# HyperRAM2.net
KiCad netlist of a schematic drawn in Altium Designer
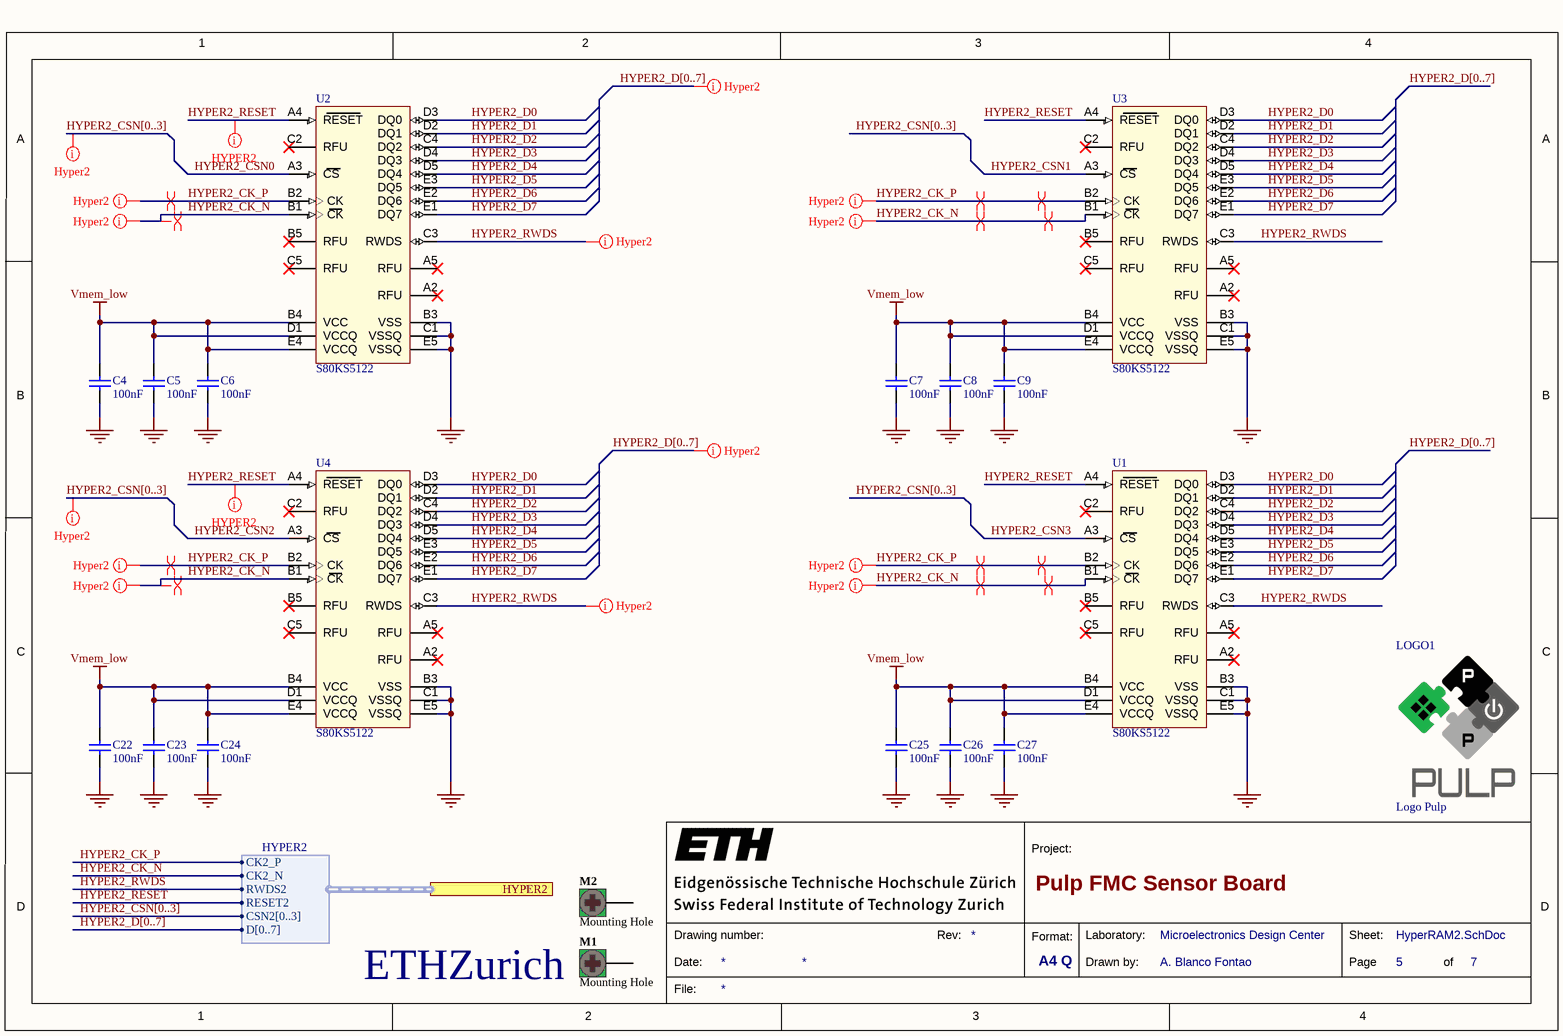
[diagram p0: HyperRAM2.SchDoc]

(export (version "E")
  (design (tool "Eeschema 10.0.6"))
  (components
    (comp (ref "A1")
      (value "Logo ETH Zurich")
      (footprint "eth-zurich_3mm")
      (libsource (lib "ETHZ Vault") (part "CMP-00038-1"))
    )
    (comp (ref "C4")
      (value "100nF")
      (footprint "CAPC0603(1608)100_N")
      (description "CAP 100nF 25V ±10% 0603 (1608 Metric) Thickness 1mm SMD")
      (fields (field (name "TOLERANCE") "Â±10%") (field (name "Comment") "CAP 100nF 25V 0603(1608)"))
      (libsource (lib "Altium Content Vault") (part "CMP-1035-02588-1"))
    )
    (comp (ref "C5")
      (value "100nF")
      (footprint "CAPC0603(1608)100_N")
      (description "CAP 100nF 25V ±10% 0603 (1608 Metric) Thickness 1mm SMD")
      (fields (field (name "TOLERANCE") "Â±10%") (field (name "Comment") "CAP 100nF 25V 0603(1608)"))
      (libsource (lib "Altium Content Vault") (part "CMP-1035-02588-1"))
    )
    (comp (ref "C6")
      (value "100nF")
      (footprint "CAPC0603(1608)100_N")
      (description "CAP 100nF 25V ±10% 0603 (1608 Metric) Thickness 1mm SMD")
      (fields (field (name "TOLERANCE") "Â±10%") (field (name "Comment") "CAP 100nF 25V 0603(1608)"))
      (libsource (lib "Altium Content Vault") (part "CMP-1035-02588-1"))
    )
    (comp (ref "C7")
      (value "100nF")
      (footprint "CAPC0603(1608)100_N")
      (description "CAP 100nF 25V ±10% 0603 (1608 Metric) Thickness 1mm SMD")
      (fields (field (name "TOLERANCE") "Â±10%") (field (name "Comment") "CAP 100nF 25V 0603(1608)"))
      (libsource (lib "Altium Content Vault") (part "CMP-1035-02588-1"))
    )
    (comp (ref "C8")
      (value "100nF")
      (footprint "CAPC0603(1608)100_N")
      (description "CAP 100nF 25V ±10% 0603 (1608 Metric) Thickness 1mm SMD")
      (fields (field (name "TOLERANCE") "Â±10%") (field (name "Comment") "CAP 100nF 25V 0603(1608)"))
      (libsource (lib "Altium Content Vault") (part "CMP-1035-02588-1"))
    )
    (comp (ref "C9")
      (value "100nF")
      (footprint "CAPC0603(1608)100_N")
      (description "CAP 100nF 25V ±10% 0603 (1608 Metric) Thickness 1mm SMD")
      (fields (field (name "TOLERANCE") "Â±10%") (field (name "Comment") "CAP 100nF 25V 0603(1608)"))
      (libsource (lib "Altium Content Vault") (part "CMP-1035-02588-1"))
    )
    (comp (ref "C22")
      (value "100nF")
      (footprint "CAPC0603(1608)100_N")
      (description "CAP 100nF 25V ±10% 0603 (1608 Metric) Thickness 1mm SMD")
      (fields (field (name "TOLERANCE") "Â±10%") (field (name "Comment") "CAP 100nF 25V 0603(1608)"))
      (libsource (lib "Altium Content Vault") (part "CMP-1035-02588-1"))
    )
    (comp (ref "C23")
      (value "100nF")
      (footprint "CAPC0603(1608)100_N")
      (description "CAP 100nF 25V ±10% 0603 (1608 Metric) Thickness 1mm SMD")
      (fields (field (name "TOLERANCE") "Â±10%") (field (name "Comment") "CAP 100nF 25V 0603(1608)"))
      (libsource (lib "Altium Content Vault") (part "CMP-1035-02588-1"))
    )
    (comp (ref "C24")
      (value "100nF")
      (footprint "CAPC0603(1608)100_N")
      (description "CAP 100nF 25V ±10% 0603 (1608 Metric) Thickness 1mm SMD")
      (fields (field (name "TOLERANCE") "Â±10%") (field (name "Comment") "CAP 100nF 25V 0603(1608)"))
      (libsource (lib "Altium Content Vault") (part "CMP-1035-02588-1"))
    )
    (comp (ref "C25")
      (value "100nF")
      (footprint "CAPC0603(1608)100_N")
      (description "CAP 100nF 25V ±10% 0603 (1608 Metric) Thickness 1mm SMD")
      (fields (field (name "TOLERANCE") "Â±10%") (field (name "Comment") "CAP 100nF 25V 0603(1608)"))
      (libsource (lib "Altium Content Vault") (part "CMP-1035-02588-1"))
    )
    (comp (ref "C26")
      (value "100nF")
      (footprint "CAPC0603(1608)100_N")
      (description "CAP 100nF 25V ±10% 0603 (1608 Metric) Thickness 1mm SMD")
      (fields (field (name "TOLERANCE") "Â±10%") (field (name "Comment") "CAP 100nF 25V 0603(1608)"))
      (libsource (lib "Altium Content Vault") (part "CMP-1035-02588-1"))
    )
    (comp (ref "C27")
      (value "100nF")
      (footprint "CAPC0603(1608)100_N")
      (description "CAP 100nF 25V ±10% 0603 (1608 Metric) Thickness 1mm SMD")
      (fields (field (name "TOLERANCE") "Â±10%") (field (name "Comment") "CAP 100nF 25V 0603(1608)"))
      (libsource (lib "Altium Content Vault") (part "CMP-1035-02588-1"))
    )
    (comp (ref "LOGO1")
      (value "Logo Pulp")
      (footprint "Logo Pulp")
      (description "4 Layers: only valid for layer stack as defined for the TestBoards")
      (libsource (lib "ETHZ Vault") (part "CMP-00145-1"))
    )
    (comp (ref "M1")
      (value "Mounting Hole")
      (footprint "Hole M3")
      (description "Mounting Hole, 7.2mm pad, 3.2mm plated hole")
      (libsource (lib "ETHZ Vault") (part "Hole"))
    )
    (comp (ref "M2")
      (value "Mounting Hole")
      (footprint "Hole M3")
      (description "Mounting Hole, 7.2mm pad, 3.2mm plated hole")
      (libsource (lib "ETHZ Vault") (part "Hole"))
    )
    (comp (ref "U1")
      (value "S80KS5122")
      (footprint "FBGA24_A-130")
      (description "512 Mb: HYPERRAM™ self-refresh dynamic\r\nRAM (DRAM) with HYPERBUS™ interface\r\n1.8 V")
      (libsource (lib "hyperRAM") (part "S80KS5122"))
    )
    (comp (ref "U2")
      (value "S80KS5122")
      (footprint "FBGA24_A-130")
      (description "512 Mb: HYPERRAM™ self-refresh dynamic\r\nRAM (DRAM) with HYPERBUS™ interface\r\n1.8 V")
      (libsource (lib "hyperRAM") (part "S80KS5122"))
    )
    (comp (ref "U3")
      (value "S80KS5122")
      (footprint "FBGA24_A-130")
      (description "512 Mb: HYPERRAM™ self-refresh dynamic\r\nRAM (DRAM) with HYPERBUS™ interface\r\n1.8 V")
      (libsource (lib "hyperRAM") (part "S80KS5122"))
    )
    (comp (ref "U4")
      (value "S80KS5122")
      (footprint "FBGA24_A-130")
      (description "512 Mb: HYPERRAM™ self-refresh dynamic\r\nRAM (DRAM) with HYPERBUS™ interface\r\n1.8 V")
      (libsource (lib "hyperRAM") (part "S80KS5122"))
    )
  )
  (nets
    (net (code "2") (name "/HYPER2_CK_N") (class "Default")
      (node (ref "U1") (pin "B1") (pinfunction "CK_B1") (pintype "input"))
      (node (ref "U2") (pin "B1") (pinfunction "CK_B1") (pintype "input"))
      (node (ref "U3") (pin "B1") (pinfunction "CK_B1") (pintype "input"))
      (node (ref "U4") (pin "B1") (pinfunction "CK_B1") (pintype "input"))
    )
    (net (code "3") (name "/HYPER2_CK_P") (class "Default")
      (node (ref "U1") (pin "B2") (pinfunction "CK_B2") (pintype "input"))
      (node (ref "U2") (pin "B2") (pinfunction "CK_B2") (pintype "input"))
      (node (ref "U3") (pin "B2") (pinfunction "CK_B2") (pintype "input"))
      (node (ref "U4") (pin "B2") (pinfunction "CK_B2") (pintype "input"))
    )
    (net (code "4") (name "/HYPER2_CSN0") (class "Default")
      (node (ref "U2") (pin "A3") (pinfunction "CS_A3") (pintype "input"))
    )
    (net (code "5") (name "/HYPER2_CSN1") (class "Default")
      (node (ref "U3") (pin "A3") (pinfunction "CS_A3") (pintype "input"))
    )
    (net (code "6") (name "/HYPER2_CSN2") (class "Default")
      (node (ref "U4") (pin "A3") (pinfunction "CS_A3") (pintype "input"))
    )
    (net (code "7") (name "/HYPER2_CSN3") (class "Default")
      (node (ref "U1") (pin "A3") (pinfunction "CS_A3") (pintype "input"))
    )
    (net (code "9") (name "/HYPER2_D0") (class "Default")
      (node (ref "U1") (pin "D3") (pinfunction "DQ0_D3") (pintype "bidirectional"))
      (node (ref "U2") (pin "D3") (pinfunction "DQ0_D3") (pintype "bidirectional"))
      (node (ref "U3") (pin "D3") (pinfunction "DQ0_D3") (pintype "bidirectional"))
      (node (ref "U4") (pin "D3") (pinfunction "DQ0_D3") (pintype "bidirectional"))
    )
    (net (code "10") (name "/HYPER2_D1") (class "Default")
      (node (ref "U1") (pin "D2") (pinfunction "DQ1_D2") (pintype "bidirectional"))
      (node (ref "U2") (pin "D2") (pinfunction "DQ1_D2") (pintype "bidirectional"))
      (node (ref "U3") (pin "D2") (pinfunction "DQ1_D2") (pintype "bidirectional"))
      (node (ref "U4") (pin "D2") (pinfunction "DQ1_D2") (pintype "bidirectional"))
    )
    (net (code "11") (name "/HYPER2_D2") (class "Default")
      (node (ref "U1") (pin "C4") (pinfunction "DQ2_C4") (pintype "bidirectional"))
      (node (ref "U2") (pin "C4") (pinfunction "DQ2_C4") (pintype "bidirectional"))
      (node (ref "U3") (pin "C4") (pinfunction "DQ2_C4") (pintype "bidirectional"))
      (node (ref "U4") (pin "C4") (pinfunction "DQ2_C4") (pintype "bidirectional"))
    )
    (net (code "12") (name "/HYPER2_D3") (class "Default")
      (node (ref "U1") (pin "D4") (pinfunction "DQ3_D4") (pintype "bidirectional"))
      (node (ref "U2") (pin "D4") (pinfunction "DQ3_D4") (pintype "bidirectional"))
      (node (ref "U3") (pin "D4") (pinfunction "DQ3_D4") (pintype "bidirectional"))
      (node (ref "U4") (pin "D4") (pinfunction "DQ3_D4") (pintype "bidirectional"))
    )
    (net (code "13") (name "/HYPER2_D4") (class "Default")
      (node (ref "U1") (pin "D5") (pinfunction "DQ4_D5") (pintype "bidirectional"))
      (node (ref "U2") (pin "D5") (pinfunction "DQ4_D5") (pintype "bidirectional"))
      (node (ref "U3") (pin "D5") (pinfunction "DQ4_D5") (pintype "bidirectional"))
      (node (ref "U4") (pin "D5") (pinfunction "DQ4_D5") (pintype "bidirectional"))
    )
    (net (code "14") (name "/HYPER2_D5") (class "Default")
      (node (ref "U1") (pin "E3") (pinfunction "DQ5_E3") (pintype "bidirectional"))
      (node (ref "U2") (pin "E3") (pinfunction "DQ5_E3") (pintype "bidirectional"))
      (node (ref "U3") (pin "E3") (pinfunction "DQ5_E3") (pintype "bidirectional"))
      (node (ref "U4") (pin "E3") (pinfunction "DQ5_E3") (pintype "bidirectional"))
    )
    (net (code "15") (name "/HYPER2_D6") (class "Default")
      (node (ref "U1") (pin "E2") (pinfunction "DQ6_E2") (pintype "bidirectional"))
      (node (ref "U2") (pin "E2") (pinfunction "DQ6_E2") (pintype "bidirectional"))
      (node (ref "U3") (pin "E2") (pinfunction "DQ6_E2") (pintype "bidirectional"))
      (node (ref "U4") (pin "E2") (pinfunction "DQ6_E2") (pintype "bidirectional"))
    )
    (net (code "16") (name "/HYPER2_D7") (class "Default")
      (node (ref "U1") (pin "E1") (pinfunction "DQ7_E1") (pintype "bidirectional"))
      (node (ref "U2") (pin "E1") (pinfunction "DQ7_E1") (pintype "bidirectional"))
      (node (ref "U3") (pin "E1") (pinfunction "DQ7_E1") (pintype "bidirectional"))
      (node (ref "U4") (pin "E1") (pinfunction "DQ7_E1") (pintype "bidirectional"))
    )
    (net (code "18") (name "/HYPER2_RESET") (class "Default")
      (node (ref "U1") (pin "A4") (pinfunction "RESET_A4") (pintype "input"))
      (node (ref "U2") (pin "A4") (pinfunction "RESET_A4") (pintype "input"))
      (node (ref "U3") (pin "A4") (pinfunction "RESET_A4") (pintype "input"))
      (node (ref "U4") (pin "A4") (pinfunction "RESET_A4") (pintype "input"))
    )
    (net (code "19") (name "/HYPER2_RWDS") (class "Default")
      (node (ref "U1") (pin "C3") (pinfunction "RWDS_C3") (pintype "bidirectional"))
      (node (ref "U2") (pin "C3") (pinfunction "RWDS_C3") (pintype "bidirectional"))
      (node (ref "U3") (pin "C3") (pinfunction "RWDS_C3") (pintype "bidirectional"))
      (node (ref "U4") (pin "C3") (pinfunction "RWDS_C3") (pintype "bidirectional"))
    )
    (net (code "21") (name "GND") (class "Default")
      (node (ref "C22") (pin "1") (pinfunction "1_1") (pintype "passive"))
      (node (ref "C23") (pin "1") (pinfunction "1_1") (pintype "passive"))
      (node (ref "C24") (pin "1") (pinfunction "1_1") (pintype "passive"))
      (node (ref "C25") (pin "1") (pinfunction "1_1") (pintype "passive"))
      (node (ref "C26") (pin "1") (pinfunction "1_1") (pintype "passive"))
      (node (ref "C27") (pin "1") (pinfunction "1_1") (pintype "passive"))
      (node (ref "C4") (pin "1") (pinfunction "1_1") (pintype "passive"))
      (node (ref "C5") (pin "1") (pinfunction "1_1") (pintype "passive"))
      (node (ref "C6") (pin "1") (pinfunction "1_1") (pintype "passive"))
      (node (ref "C7") (pin "1") (pinfunction "1_1") (pintype "passive"))
      (node (ref "C8") (pin "1") (pinfunction "1_1") (pintype "passive"))
      (node (ref "C9") (pin "1") (pinfunction "1_1") (pintype "passive"))
      (node (ref "U1") (pin "B3") (pinfunction "VSS_B3") (pintype "passive"))
      (node (ref "U1") (pin "C1") (pinfunction "VSSQ_C1") (pintype "passive"))
      (node (ref "U1") (pin "E5") (pinfunction "VSSQ_E5") (pintype "passive"))
      (node (ref "U2") (pin "B3") (pinfunction "VSS_B3") (pintype "passive"))
      (node (ref "U2") (pin "C1") (pinfunction "VSSQ_C1") (pintype "passive"))
      (node (ref "U2") (pin "E5") (pinfunction "VSSQ_E5") (pintype "passive"))
      (node (ref "U3") (pin "B3") (pinfunction "VSS_B3") (pintype "passive"))
      (node (ref "U3") (pin "C1") (pinfunction "VSSQ_C1") (pintype "passive"))
      (node (ref "U3") (pin "E5") (pinfunction "VSSQ_E5") (pintype "passive"))
      (node (ref "U4") (pin "B3") (pinfunction "VSS_B3") (pintype "passive"))
      (node (ref "U4") (pin "C1") (pinfunction "VSSQ_C1") (pintype "passive"))
      (node (ref "U4") (pin "E5") (pinfunction "VSSQ_E5") (pintype "passive"))
    )
    (net (code "22") (name "Vmem_low") (class "Default")
      (node (ref "C22") (pin "2") (pinfunction "2_2") (pintype "passive"))
      (node (ref "C23") (pin "2") (pinfunction "2_2") (pintype "passive"))
      (node (ref "C24") (pin "2") (pinfunction "2_2") (pintype "passive"))
      (node (ref "C25") (pin "2") (pinfunction "2_2") (pintype "passive"))
      (node (ref "C26") (pin "2") (pinfunction "2_2") (pintype "passive"))
      (node (ref "C27") (pin "2") (pinfunction "2_2") (pintype "passive"))
      (node (ref "C4") (pin "2") (pinfunction "2_2") (pintype "passive"))
      (node (ref "C5") (pin "2") (pinfunction "2_2") (pintype "passive"))
      (node (ref "C6") (pin "2") (pinfunction "2_2") (pintype "passive"))
      (node (ref "C7") (pin "2") (pinfunction "2_2") (pintype "passive"))
      (node (ref "C8") (pin "2") (pinfunction "2_2") (pintype "passive"))
      (node (ref "C9") (pin "2") (pinfunction "2_2") (pintype "passive"))
      (node (ref "U1") (pin "B4") (pinfunction "VCC_B4") (pintype "passive"))
      (node (ref "U1") (pin "D1") (pinfunction "VCCQ_D1") (pintype "passive"))
      (node (ref "U1") (pin "E4") (pinfunction "VCCQ_E4") (pintype "passive"))
      (node (ref "U2") (pin "B4") (pinfunction "VCC_B4") (pintype "passive"))
      (node (ref "U2") (pin "D1") (pinfunction "VCCQ_D1") (pintype "passive"))
      (node (ref "U2") (pin "E4") (pinfunction "VCCQ_E4") (pintype "passive"))
      (node (ref "U3") (pin "B4") (pinfunction "VCC_B4") (pintype "passive"))
      (node (ref "U3") (pin "D1") (pinfunction "VCCQ_D1") (pintype "passive"))
      (node (ref "U3") (pin "E4") (pinfunction "VCCQ_E4") (pintype "passive"))
      (node (ref "U4") (pin "B4") (pinfunction "VCC_B4") (pintype "passive"))
      (node (ref "U4") (pin "D1") (pinfunction "VCCQ_D1") (pintype "passive"))
      (node (ref "U4") (pin "E4") (pinfunction "VCCQ_E4") (pintype "passive"))
    )
    (net (code "23") (name "unconnected-(M1-Pad1)") (class "Default")
      (node (ref "M1") (pin "1") (pinfunction "1_1") (pintype "passive"))
    )
    (net (code "24") (name "unconnected-(M2-Pad1)") (class "Default")
      (node (ref "M2") (pin "1") (pinfunction "1_1") (pintype "passive"))
    )
    (net (code "25") (name "unconnected-(U1-RFU-PadA2)") (class "Default")
      (node (ref "U1") (pin "A2") (pinfunction "RFU_A2") (pintype "passive+no_connect"))
    )
    (net (code "26") (name "unconnected-(U1-RFU-PadA5)") (class "Default")
      (node (ref "U1") (pin "A5") (pinfunction "RFU_A5") (pintype "passive+no_connect"))
    )
    (net (code "27") (name "unconnected-(U1-RFU-PadB5)") (class "Default")
      (node (ref "U1") (pin "B5") (pinfunction "RFU_B5") (pintype "passive+no_connect"))
    )
    (net (code "28") (name "unconnected-(U1-RFU-PadC2)") (class "Default")
      (node (ref "U1") (pin "C2") (pinfunction "RFU_C2") (pintype "passive+no_connect"))
    )
    (net (code "29") (name "unconnected-(U1-RFU-PadC5)") (class "Default")
      (node (ref "U1") (pin "C5") (pinfunction "RFU_C5") (pintype "passive+no_connect"))
    )
    (net (code "30") (name "unconnected-(U2-RFU-PadA2)") (class "Default")
      (node (ref "U2") (pin "A2") (pinfunction "RFU_A2") (pintype "passive+no_connect"))
    )
    (net (code "31") (name "unconnected-(U2-RFU-PadA5)") (class "Default")
      (node (ref "U2") (pin "A5") (pinfunction "RFU_A5") (pintype "passive+no_connect"))
    )
    (net (code "32") (name "unconnected-(U2-RFU-PadB5)") (class "Default")
      (node (ref "U2") (pin "B5") (pinfunction "RFU_B5") (pintype "passive+no_connect"))
    )
    (net (code "33") (name "unconnected-(U2-RFU-PadC2)") (class "Default")
      (node (ref "U2") (pin "C2") (pinfunction "RFU_C2") (pintype "passive+no_connect"))
    )
    (net (code "34") (name "unconnected-(U2-RFU-PadC5)") (class "Default")
      (node (ref "U2") (pin "C5") (pinfunction "RFU_C5") (pintype "passive+no_connect"))
    )
    (net (code "35") (name "unconnected-(U3-RFU-PadA2)") (class "Default")
      (node (ref "U3") (pin "A2") (pinfunction "RFU_A2") (pintype "passive+no_connect"))
    )
    (net (code "36") (name "unconnected-(U3-RFU-PadA5)") (class "Default")
      (node (ref "U3") (pin "A5") (pinfunction "RFU_A5") (pintype "passive+no_connect"))
    )
    (net (code "37") (name "unconnected-(U3-RFU-PadB5)") (class "Default")
      (node (ref "U3") (pin "B5") (pinfunction "RFU_B5") (pintype "passive+no_connect"))
    )
    (net (code "38") (name "unconnected-(U3-RFU-PadC2)") (class "Default")
      (node (ref "U3") (pin "C2") (pinfunction "RFU_C2") (pintype "passive+no_connect"))
    )
    (net (code "39") (name "unconnected-(U3-RFU-PadC5)") (class "Default")
      (node (ref "U3") (pin "C5") (pinfunction "RFU_C5") (pintype "passive+no_connect"))
    )
    (net (code "40") (name "unconnected-(U4-RFU-PadA2)") (class "Default")
      (node (ref "U4") (pin "A2") (pinfunction "RFU_A2") (pintype "passive+no_connect"))
    )
    (net (code "41") (name "unconnected-(U4-RFU-PadA5)") (class "Default")
      (node (ref "U4") (pin "A5") (pinfunction "RFU_A5") (pintype "passive+no_connect"))
    )
    (net (code "42") (name "unconnected-(U4-RFU-PadB5)") (class "Default")
      (node (ref "U4") (pin "B5") (pinfunction "RFU_B5") (pintype "passive+no_connect"))
    )
    (net (code "43") (name "unconnected-(U4-RFU-PadC2)") (class "Default")
      (node (ref "U4") (pin "C2") (pinfunction "RFU_C2") (pintype "passive+no_connect"))
    )
    (net (code "44") (name "unconnected-(U4-RFU-PadC5)") (class "Default")
      (node (ref "U4") (pin "C5") (pinfunction "RFU_C5") (pintype "passive+no_connect"))
    )
  )
)
